# circuit.net
KiCad netlist of a schematic drawn in EAGLE
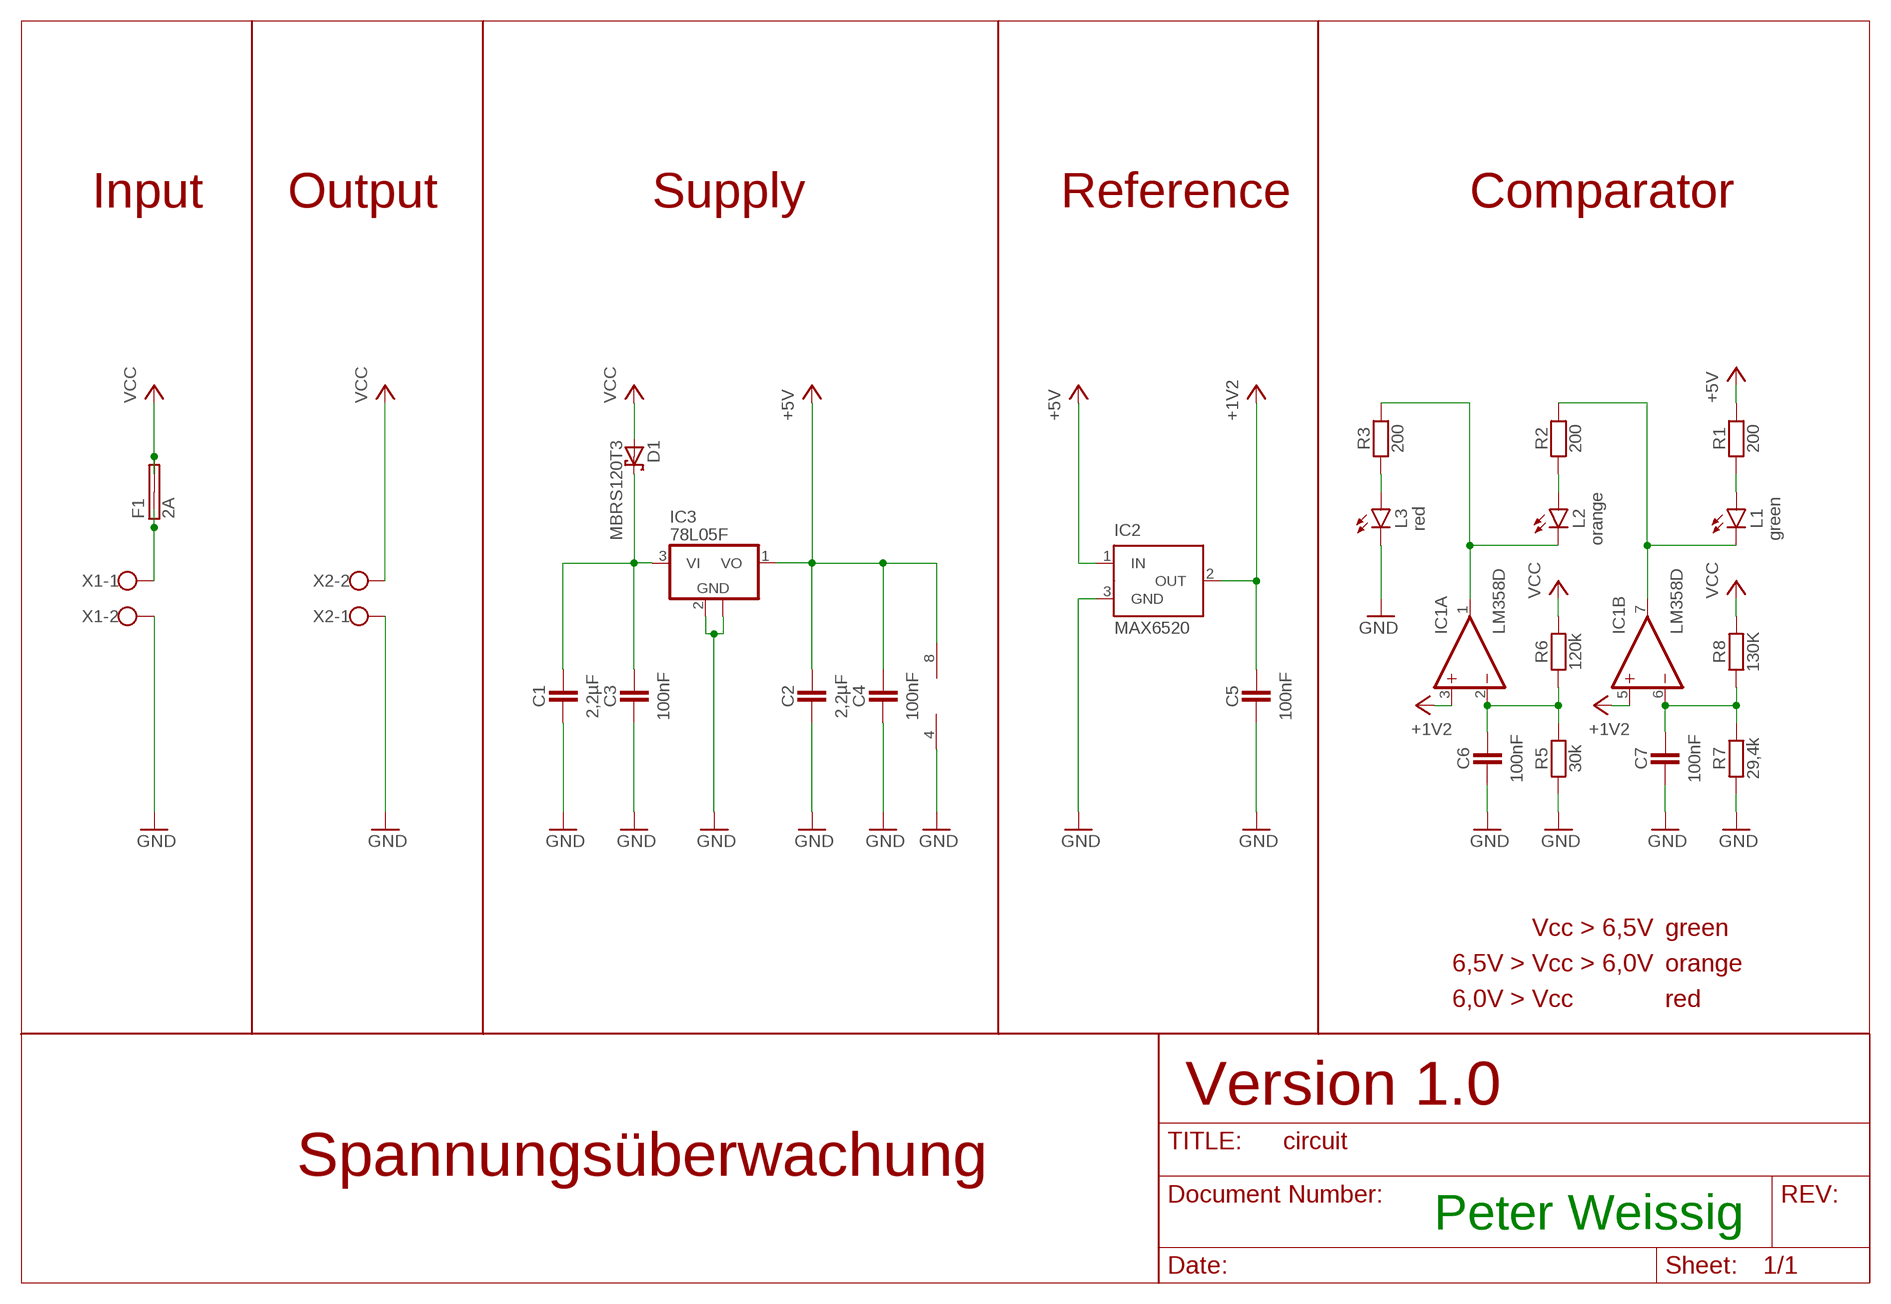
[diagram p0: schematic, sheet 1]

(export (version "E")
  (design (tool "Eeschema 10.0.6"))
  (components
    (comp (ref "C1")
      (value "2,2µF")
      (footprint "eagle-import:SMD_1206")
      (libsource (lib "eagle-import") (part "CAPACITATOR-1206"))
    )
    (comp (ref "C2")
      (value "2,2µF")
      (footprint "eagle-import:SMD_1206")
      (libsource (lib "eagle-import") (part "CAPACITATOR-1206"))
    )
    (comp (ref "C3")
      (value "100nF")
      (footprint "eagle-import:SMD_1206")
      (libsource (lib "eagle-import") (part "CAPACITATOR-1206"))
    )
    (comp (ref "C4")
      (value "100nF")
      (footprint "eagle-import:SMD_1206")
      (libsource (lib "eagle-import") (part "CAPACITATOR-1206"))
    )
    (comp (ref "C5")
      (value "100nF")
      (footprint "eagle-import:SMD_1206")
      (libsource (lib "eagle-import") (part "CAPACITATOR-1206"))
    )
    (comp (ref "C6")
      (value "100nF")
      (footprint "eagle-import:SMD_1206")
      (libsource (lib "eagle-import") (part "CAPACITATOR-1206"))
    )
    (comp (ref "C7")
      (value "100nF")
      (footprint "eagle-import:SMD_1206")
      (libsource (lib "eagle-import") (part "CAPACITATOR-1206"))
    )
    (comp (ref "D1")
      (value "MBRS120T3")
      (footprint "eagle-import:SMB")
      (libsource (lib "eagle-import") (part "MBRS130LT3"))
    )
    (comp (ref "F1")
      (value "2A")
      (footprint "eagle-import:SHK20L")
      (libsource (lib "eagle-import") (part "SHK20L"))
    )
    (comp (ref "IC1")
      (value "LM358D")
      (footprint "eagle-import:SO08")
      (libsource (lib "eagle-import") (part "LM358D"))
    )
    (comp (ref "IC2")
      (value "MAX6520")
      (footprint "eagle-import:SOT23")
      (fields (field (name "MF") "MAXIM") (field (name "MPN") "MAX6520EUR-T"))
      (libsource (lib "eagle-import") (part "MAX6520"))
    )
    (comp (ref "IC3")
      (value "78L05F")
      (footprint "eagle-import:SOT89")
      (libsource (lib "eagle-import") (part "78LF05"))
    )
    (comp (ref "L1")
      (value "green")
      (footprint "eagle-import:LED_3MM")
      (libsource (lib "eagle-import") (part "LED-3MM"))
    )
    (comp (ref "L2")
      (value "orange")
      (footprint "eagle-import:LED_3MM")
      (libsource (lib "eagle-import") (part "LED-3MM"))
    )
    (comp (ref "L3")
      (value "red")
      (footprint "eagle-import:LED_3MM")
      (libsource (lib "eagle-import") (part "LED-3MM"))
    )
    (comp (ref "R1")
      (value "200")
      (footprint "eagle-import:SMD_1206")
      (libsource (lib "eagle-import") (part "RESISTOR-1206"))
    )
    (comp (ref "R2")
      (value "200")
      (footprint "eagle-import:SMD_1206")
      (libsource (lib "eagle-import") (part "RESISTOR-1206"))
    )
    (comp (ref "R3")
      (value "200")
      (footprint "eagle-import:SMD_1206")
      (libsource (lib "eagle-import") (part "RESISTOR-1206"))
    )
    (comp (ref "R5")
      (value "30k")
      (footprint "eagle-import:SMD_1206")
      (libsource (lib "eagle-import") (part "RESISTOR-1206"))
    )
    (comp (ref "R6")
      (value "120k")
      (footprint "eagle-import:SMD_1206")
      (libsource (lib "eagle-import") (part "RESISTOR-1206"))
    )
    (comp (ref "R7")
      (value "29,4k")
      (footprint "eagle-import:SMD_1206")
      (libsource (lib "eagle-import") (part "RESISTOR-1206"))
    )
    (comp (ref "R8")
      (value "130K")
      (footprint "eagle-import:SMD_1206")
      (libsource (lib "eagle-import") (part "RESISTOR-1206"))
    )
    (comp (ref "X1")
      (value "W237-102")
      (footprint "eagle-import:W237-102")
      (fields (field (name "MPN") "237-102"))
      (libsource (lib "eagle-import") (part "W237-102"))
    )
    (comp (ref "X2")
      (value "W237-102")
      (footprint "eagle-import:W237-102")
      (fields (field (name "MPN") "237-102"))
      (libsource (lib "eagle-import") (part "W237-102"))
    )
  )
  (nets
    (net (code "1") (name "+1V2") (class "Default")
      (node (ref "C5") (pin "1") (pinfunction "1_1") (pintype "passive"))
      (node (ref "IC1") (pin "3") (pinfunction "+IN_3") (pintype "input"))
      (node (ref "IC1") (pin "5") (pinfunction "+IN_5") (pintype "input"))
      (node (ref "IC2") (pin "2") (pinfunction "OUT_2") (pintype "output"))
    )
    (net (code "2") (name "+5V") (class "Default")
      (node (ref "C2") (pin "1") (pinfunction "1_1") (pintype "passive"))
      (node (ref "C4") (pin "1") (pinfunction "1_1") (pintype "passive"))
      (node (ref "IC1") (pin "8") (pinfunction "V+_8") (pintype "power_in"))
      (node (ref "IC2") (pin "1") (pinfunction "IN_1") (pintype "input"))
      (node (ref "IC3") (pin "1") (pinfunction "VO_1") (pintype "passive"))
      (node (ref "R1") (pin "1") (pinfunction "P1_1") (pintype "passive"))
    )
    (net (code "3") (name "GND") (class "Default")
      (node (ref "C1") (pin "2") (pinfunction "2_2") (pintype "passive"))
      (node (ref "C2") (pin "2") (pinfunction "2_2") (pintype "passive"))
      (node (ref "C3") (pin "2") (pinfunction "2_2") (pintype "passive"))
      (node (ref "C4") (pin "2") (pinfunction "2_2") (pintype "passive"))
      (node (ref "C5") (pin "2") (pinfunction "2_2") (pintype "passive"))
      (node (ref "C6") (pin "2") (pinfunction "2_2") (pintype "passive"))
      (node (ref "C7") (pin "2") (pinfunction "2_2") (pintype "passive"))
      (node (ref "IC1") (pin "4") (pinfunction "V-_4") (pintype "power_in"))
      (node (ref "IC2") (pin "3") (pinfunction "GND_3") (pintype "power_in"))
      (node (ref "IC3") (pin "2") (pinfunction "GND_2") (pintype "passive"))
      (node (ref "IC3") (pin "2@1") (pinfunction "GND_2@1") (pintype "passive"))
      (node (ref "L3") (pin "K") (pinfunction "C_K") (pintype "passive"))
      (node (ref "R5") (pin "1") (pinfunction "P1_1") (pintype "passive"))
      (node (ref "R7") (pin "1") (pinfunction "P1_1") (pintype "passive"))
      (node (ref "X1") (pin "2") (pinfunction "KL_2") (pintype "passive"))
      (node (ref "X2") (pin "1") (pinfunction "KL_1") (pintype "passive"))
    )
    (net (code "4") (name "Net-(IC1A--IN)") (class "Default")
      (node (ref "C6") (pin "1") (pinfunction "1_1") (pintype "passive"))
      (node (ref "IC1") (pin "2") (pinfunction "-IN_2") (pintype "input"))
      (node (ref "R5") (pin "2") (pinfunction "P2_2") (pintype "passive"))
      (node (ref "R6") (pin "1") (pinfunction "P1_1") (pintype "passive"))
    )
    (net (code "5") (name "Net-(IC1A-OUT)") (class "Default")
      (node (ref "IC1") (pin "1") (pinfunction "OUT_1") (pintype "output"))
      (node (ref "L2") (pin "K") (pinfunction "C_K") (pintype "passive"))
      (node (ref "R3") (pin "1") (pinfunction "P1_1") (pintype "passive"))
    )
    (net (code "6") (name "Net-(IC1B--IN)") (class "Default")
      (node (ref "C7") (pin "1") (pinfunction "1_1") (pintype "passive"))
      (node (ref "IC1") (pin "6") (pinfunction "-IN_6") (pintype "input"))
      (node (ref "R7") (pin "2") (pinfunction "P2_2") (pintype "passive"))
      (node (ref "R8") (pin "1") (pinfunction "P1_1") (pintype "passive"))
    )
    (net (code "7") (name "Net-(IC1B-OUT)") (class "Default")
      (node (ref "IC1") (pin "7") (pinfunction "OUT_7") (pintype "output"))
      (node (ref "L1") (pin "K") (pinfunction "C_K") (pintype "passive"))
      (node (ref "R2") (pin "1") (pinfunction "P1_1") (pintype "passive"))
    )
    (net (code "8") (name "Net-(IC3-VI)") (class "Default")
      (node (ref "C1") (pin "1") (pinfunction "1_1") (pintype "passive"))
      (node (ref "C3") (pin "1") (pinfunction "1_1") (pintype "passive"))
      (node (ref "D1") (pin "C") (pinfunction "C_C") (pintype "passive"))
      (node (ref "IC3") (pin "3") (pinfunction "VI_3") (pintype "input"))
    )
    (net (code "9") (name "Net-(R1-P2)") (class "Default")
      (node (ref "L1") (pin "A") (pinfunction "A_A") (pintype "passive"))
      (node (ref "R1") (pin "2") (pinfunction "P2_2") (pintype "passive"))
    )
    (net (code "10") (name "Net-(R2-P2)") (class "Default")
      (node (ref "L2") (pin "A") (pinfunction "A_A") (pintype "passive"))
      (node (ref "R2") (pin "2") (pinfunction "P2_2") (pintype "passive"))
    )
    (net (code "11") (name "Net-(R3-P2)") (class "Default")
      (node (ref "L3") (pin "A") (pinfunction "A_A") (pintype "passive"))
      (node (ref "R3") (pin "2") (pinfunction "P2_2") (pintype "passive"))
    )
    (net (code "12") (name "Net-(X1A-KL)") (class "Default")
      (node (ref "F1") (pin "1A") (pinfunction "1A_1A") (pintype "passive"))
      (node (ref "F1") (pin "1B") (pinfunction "1B_1B") (pintype "passive"))
      (node (ref "X1") (pin "1") (pinfunction "KL_1") (pintype "passive"))
    )
    (net (code "13") (name "VCC") (class "Default")
      (node (ref "D1") (pin "A") (pinfunction "A_A") (pintype "passive"))
      (node (ref "F1") (pin "2A") (pinfunction "2A_2A") (pintype "passive"))
      (node (ref "F1") (pin "2B") (pinfunction "2B_2B") (pintype "passive"))
      (node (ref "R6") (pin "2") (pinfunction "P2_2") (pintype "passive"))
      (node (ref "R8") (pin "2") (pinfunction "P2_2") (pintype "passive"))
      (node (ref "X2") (pin "2") (pinfunction "KL_2") (pintype "passive"))
    )
  )
)
